# E6_Esp32_TS26C01_v2.net
KiCad netlist of a schematic drawn in EAGLE
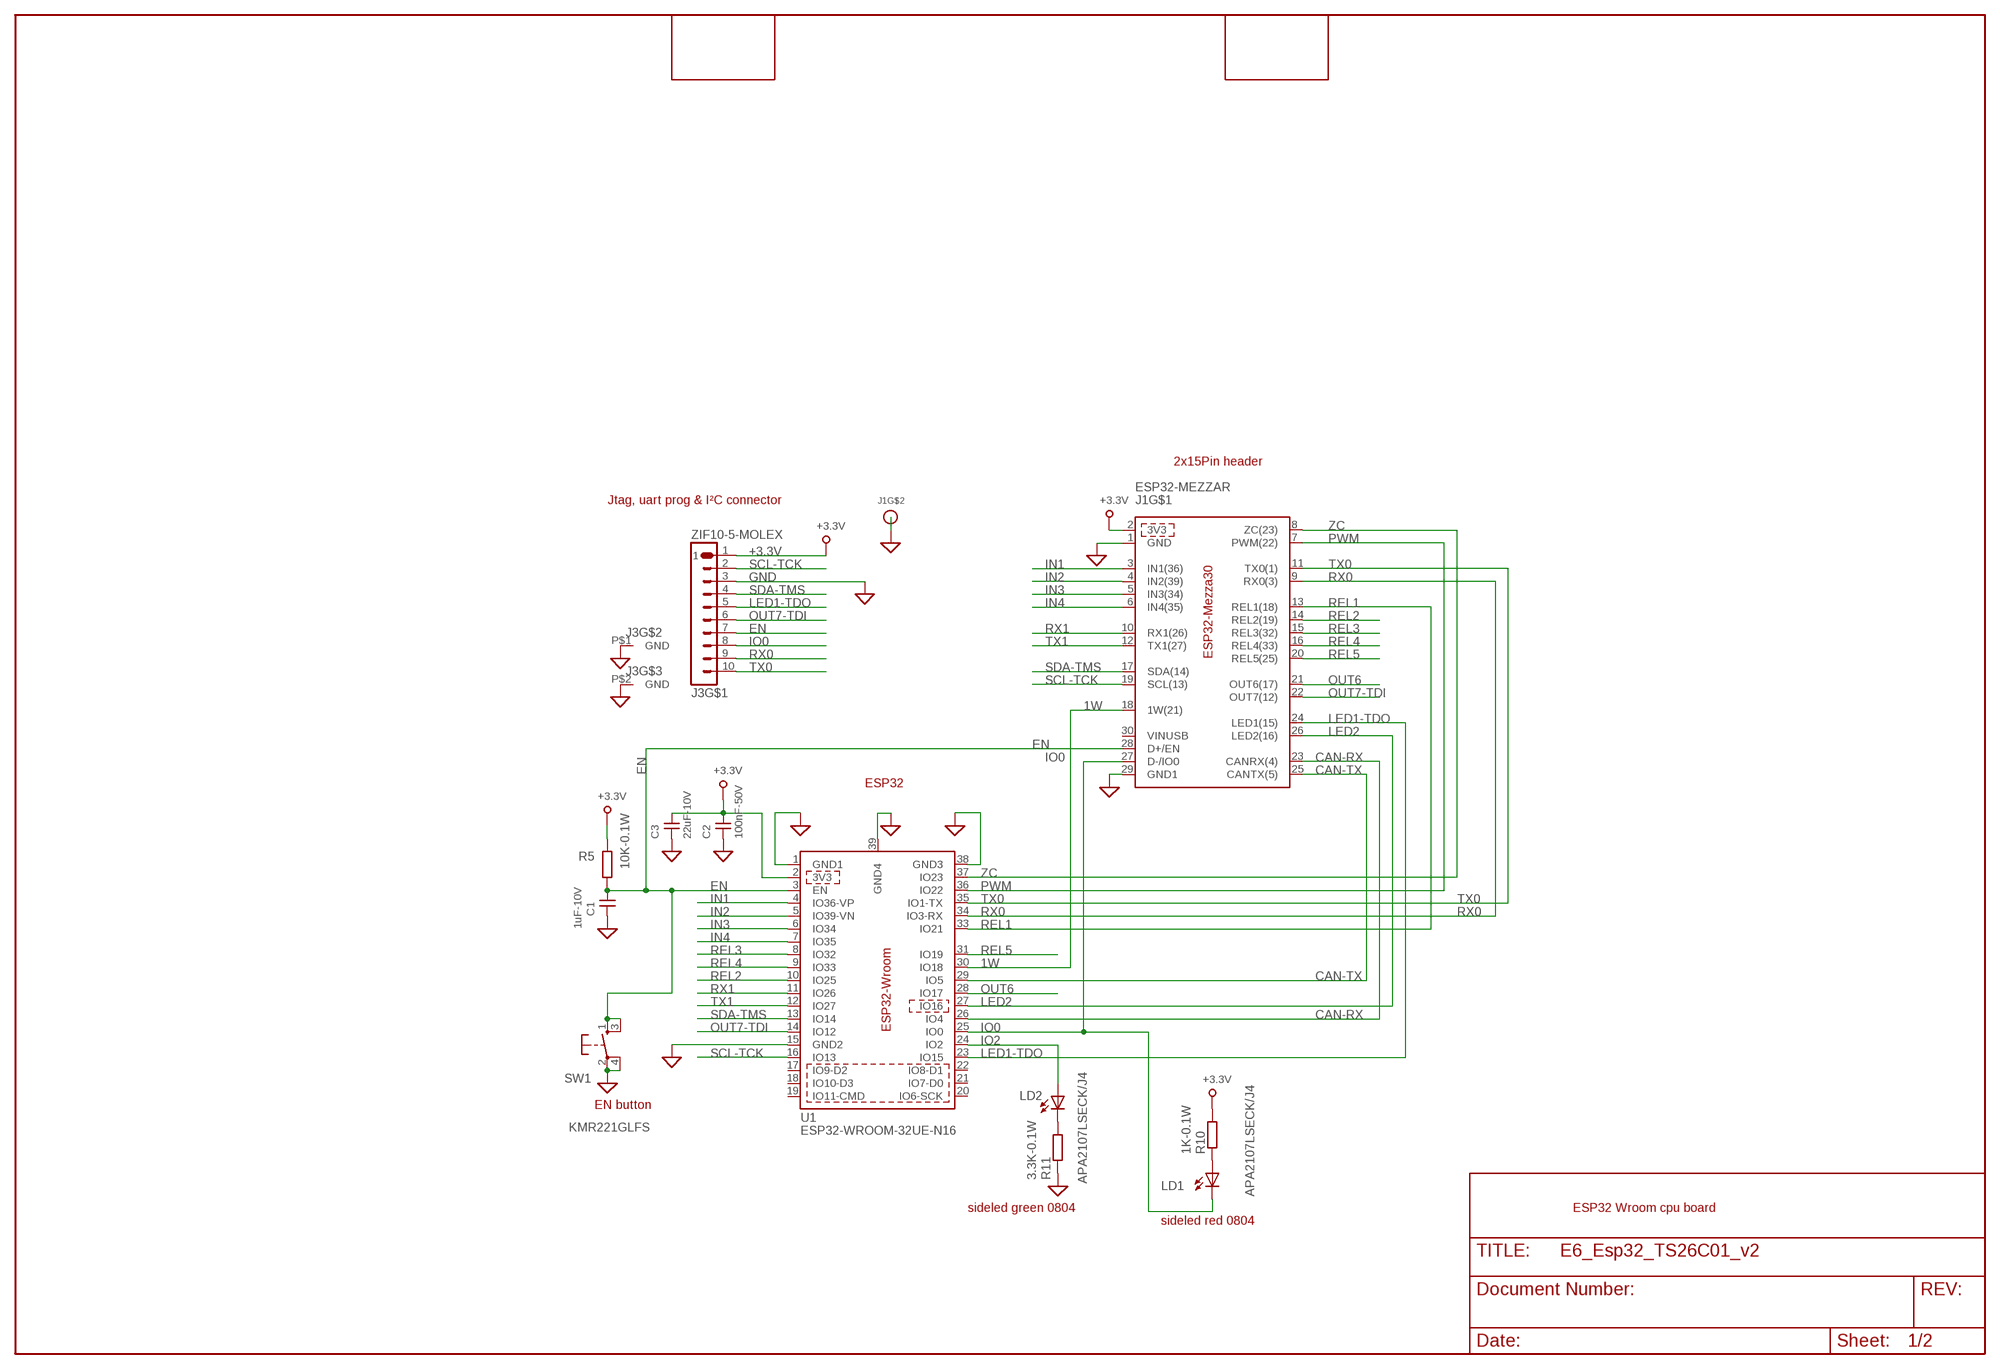
[diagram p0: schematic, sheet 1]
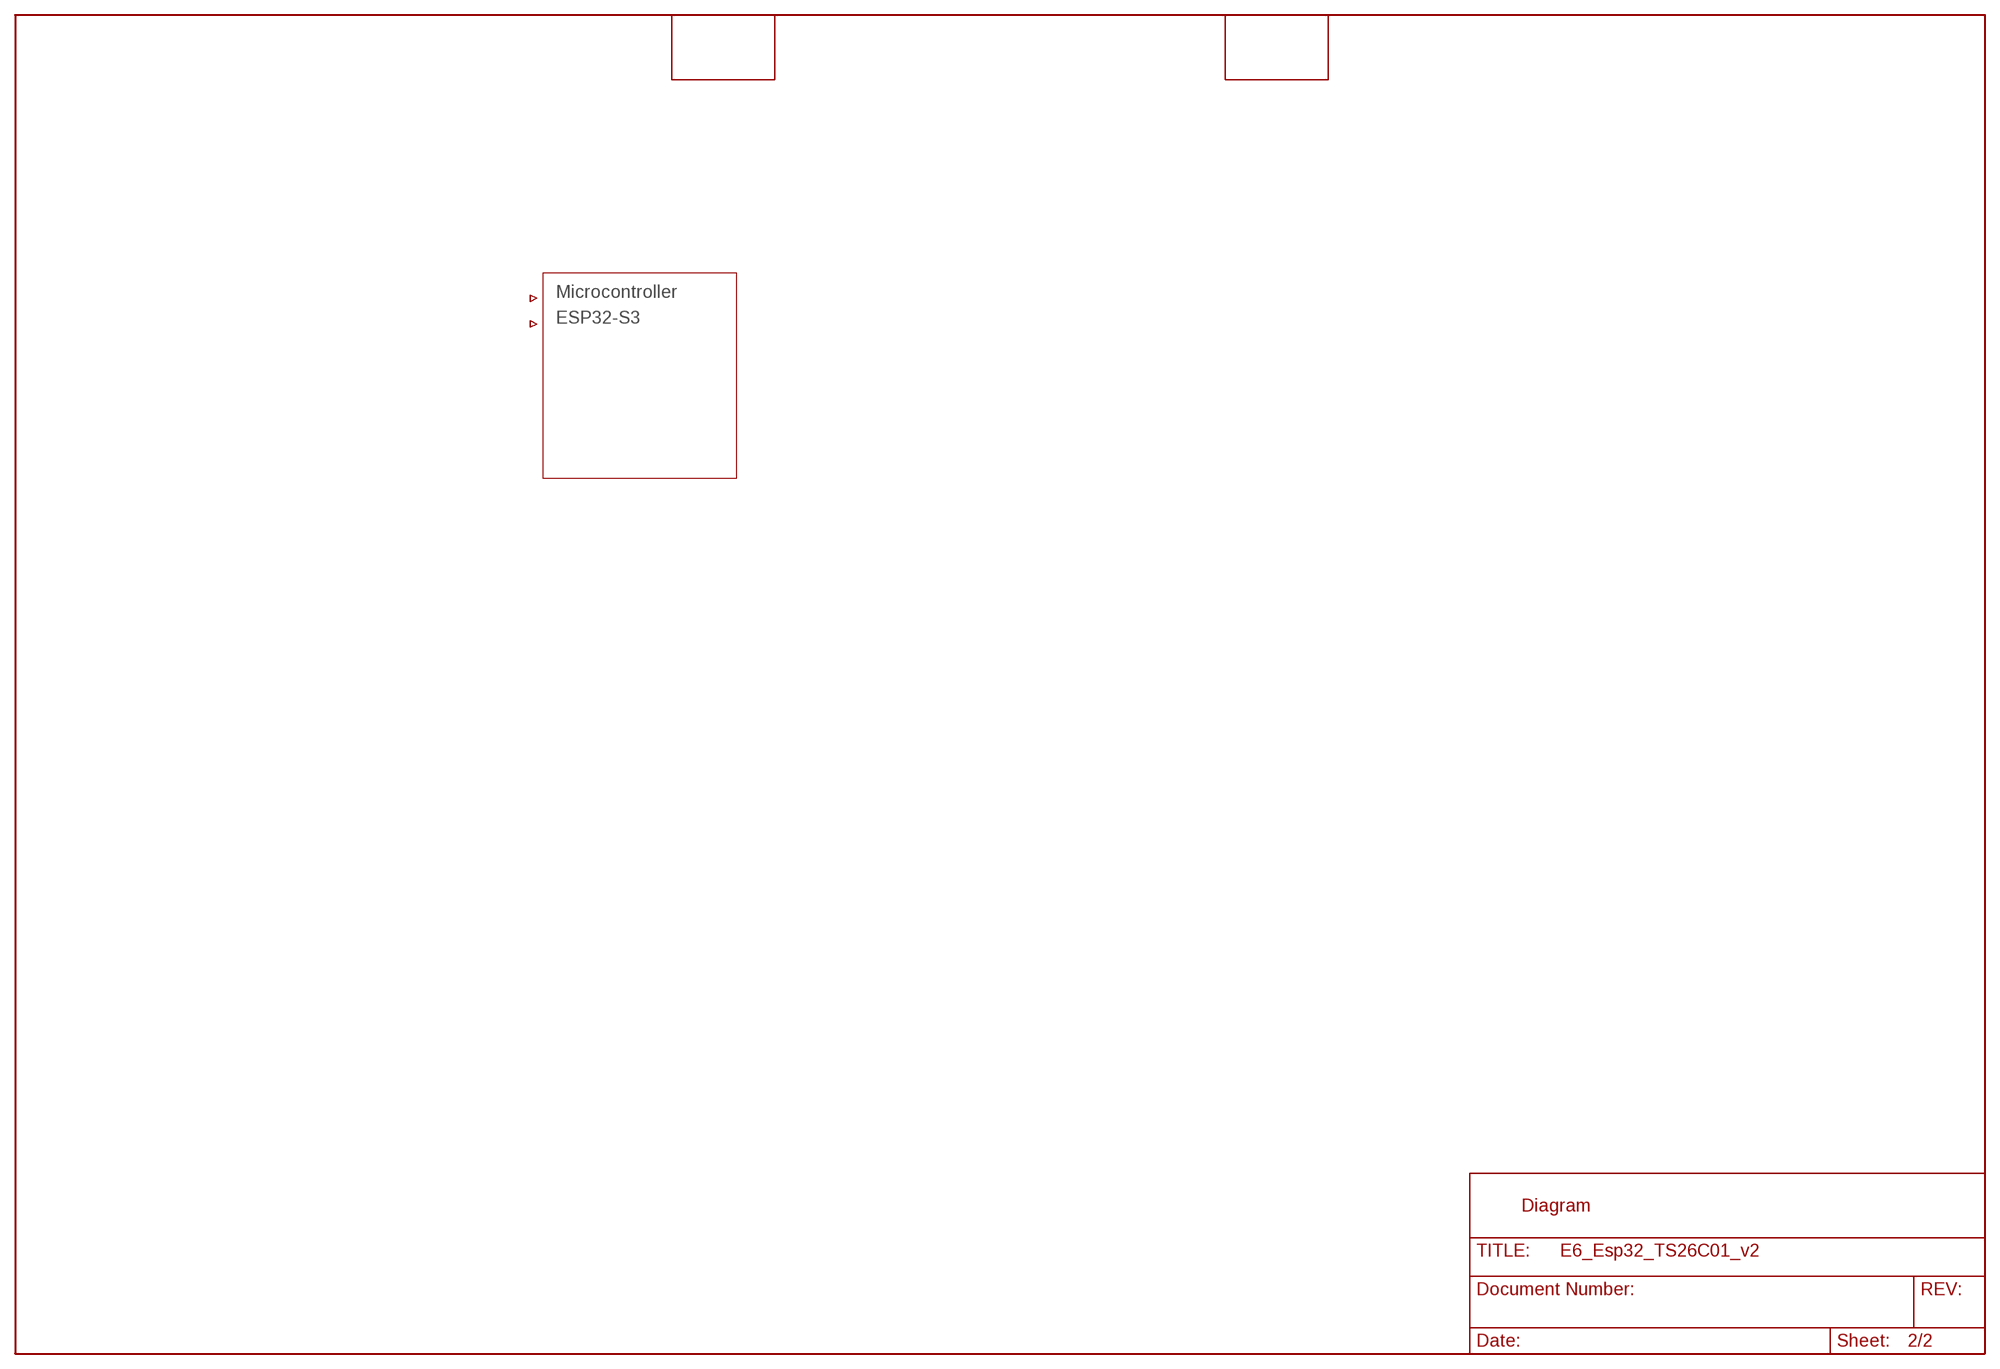
[diagram p1: schematic, sheet 2]

(export (version "E")
  (design (tool "Eeschema 10.0.6"))
  (components
    (comp (ref "C1")
      (value "1uF-10V")
      (footprint "eagle-import:C0603")
      (libsource (lib "eagle-import") (part "CAP-0603-L"))
    )
    (comp (ref "C2")
      (value "100nF-50V")
      (footprint "eagle-import:C0603")
      (libsource (lib "eagle-import") (part "CAP-0603-L"))
    )
    (comp (ref "C3")
      (value "22uF-10V")
      (footprint "eagle-import:C0603")
      (libsource (lib "eagle-import") (part "CAP-0603-L"))
    )
    (comp (ref "J1")
      (value "ESP32-MEZZAR")
      (footprint "eagle-import:ESP32-MEZZA25-R")
      (libsource (lib "eagle-import") (part "ESP32-MEZZAR"))
    )
    (comp (ref "J3")
      (value "ZIF10-5-MOLEX")
      (footprint "eagle-import:52746-1071-J")
      (libsource (lib "eagle-import") (part "ZIF10-5-MOLEXSTD"))
    )
    (comp (ref "LD1")
      (value "APA2107LSECK/J4")
      (footprint "eagle-import:SIDELED_0805")
      (libsource (lib "eagle-import") (part "SIDELED_0805"))
    )
    (comp (ref "LD2")
      (value "APA2107LSECK/J4")
      (footprint "eagle-import:SIDELED_0805")
      (libsource (lib "eagle-import") (part "SIDELED_0805"))
    )
    (comp (ref "R5")
      (value "10K-0.1W")
      (footprint "eagle-import:0603")
      (libsource (lib "eagle-import") (part "R-EU_R0603-S"))
    )
    (comp (ref "R10")
      (value "1K-0.1W")
      (footprint "eagle-import:0603")
      (libsource (lib "eagle-import") (part "R-EU_R0603-S"))
    )
    (comp (ref "R11")
      (value "3.3K-0.1W")
      (footprint "eagle-import:0603")
      (libsource (lib "eagle-import") (part "R-EU_R0603-S"))
    )
    (comp (ref "SW1")
      (value "KMR221GLFS")
      (footprint "eagle-import:SW-KMS-HOLE-NOGND")
      (libsource (lib "eagle-import") (part "SW-TACT-NOGNDSIDE"))
    )
    (comp (ref "U1")
      (value "ESP32-WROOM-32UE-N16")
      (footprint "eagle-import:ESP32-WROOM-32UE")
      (libsource (lib "eagle-import") (part "ESP32-WROOM-UE"))
    )
  )
  (nets
    (net (code "1") (name "+3.3V") (class "Default")
      (node (ref "C2") (pin "2") (pinfunction "2_2") (pintype "passive"))
      (node (ref "C3") (pin "2") (pinfunction "2_2") (pintype "passive"))
      (node (ref "J1") (pin "2") (pinfunction "3V3_2") (pintype "bidirectional"))
      (node (ref "J3") (pin "1") (pinfunction "1_1") (pintype "passive"))
      (node (ref "R10") (pin "1") (pinfunction "1_1") (pintype "passive"))
      (node (ref "R5") (pin "1") (pinfunction "1_1") (pintype "passive"))
      (node (ref "U1") (pin "2") (pinfunction "3V3_2") (pintype "power_in"))
    )
    (net (code "2") (name "1W") (class "Default")
      (node (ref "J1") (pin "18") (pinfunction "1W(21)_18") (pintype "bidirectional"))
      (node (ref "U1") (pin "30") (pinfunction "IO18_30") (pintype "bidirectional"))
    )
    (net (code "3") (name "CAN-RX") (class "Default")
      (node (ref "J1") (pin "23") (pinfunction "CANRX(4)_23") (pintype "bidirectional"))
      (node (ref "U1") (pin "26") (pinfunction "IO4_26") (pintype "bidirectional"))
    )
    (net (code "4") (name "CAN-TX") (class "Default")
      (node (ref "J1") (pin "25") (pinfunction "CANTX(5)_25") (pintype "bidirectional"))
      (node (ref "U1") (pin "29") (pinfunction "IO5_29") (pintype "bidirectional"))
    )
    (net (code "5") (name "EN") (class "Default")
      (node (ref "C1") (pin "2") (pinfunction "2_2") (pintype "passive"))
      (node (ref "J1") (pin "28") (pinfunction "D+/EN_28") (pintype "bidirectional"))
      (node (ref "J3") (pin "7") (pinfunction "7_7") (pintype "passive"))
      (node (ref "R5") (pin "2") (pinfunction "2_2") (pintype "passive"))
      (node (ref "SW1") (pin "1") (pinfunction "S_1") (pintype "passive"))
      (node (ref "SW1") (pin "3") (pinfunction "S_3") (pintype "passive"))
      (node (ref "U1") (pin "3") (pinfunction "EN_3") (pintype "bidirectional"))
    )
    (net (code "6") (name "GND") (class "Default")
      (node (ref "C1") (pin "1") (pinfunction "1_1") (pintype "passive"))
      (node (ref "C2") (pin "1") (pinfunction "1_1") (pintype "passive"))
      (node (ref "C3") (pin "1") (pinfunction "1_1") (pintype "passive"))
      (node (ref "J1") (pin "1") (pinfunction "GND_1") (pintype "power_in"))
      (node (ref "J1") (pin "29") (pinfunction "GND1_29") (pintype "power_in"))
      (node (ref "J1") (pin "31") (pinfunction "P$1_31") (pintype "passive"))
      (node (ref "J3") (pin "3") (pinfunction "3_3") (pintype "passive"))
      (node (ref "J3") (pin "P$1") (pinfunction "GND_P$1") (pintype "power_in"))
      (node (ref "J3") (pin "P$2") (pinfunction "GND_P$2") (pintype "power_in"))
      (node (ref "R11") (pin "2") (pinfunction "2_2") (pintype "passive"))
      (node (ref "SW1") (pin "2") (pinfunction "P_2") (pintype "passive"))
      (node (ref "SW1") (pin "4") (pinfunction "P_4") (pintype "passive"))
      (node (ref "U1") (pin "1") (pinfunction "GND1_1") (pintype "power_in"))
      (node (ref "U1") (pin "15") (pinfunction "GND2_15") (pintype "power_in"))
      (node (ref "U1") (pin "38") (pinfunction "GND3_38") (pintype "power_in"))
      (node (ref "U1") (pin "39") (pinfunction "GND4_39") (pintype "power_in"))
    )
    (net (code "7") (name "IN1") (class "Default")
      (node (ref "J1") (pin "3") (pinfunction "IN1(36)_3") (pintype "bidirectional"))
      (node (ref "U1") (pin "4") (pinfunction "IO36-VP_4") (pintype "bidirectional"))
    )
    (net (code "8") (name "IN2") (class "Default")
      (node (ref "J1") (pin "4") (pinfunction "IN2(39)_4") (pintype "bidirectional"))
      (node (ref "U1") (pin "5") (pinfunction "IO39-VN_5") (pintype "bidirectional"))
    )
    (net (code "9") (name "IN3") (class "Default")
      (node (ref "J1") (pin "5") (pinfunction "IN3(34)_5") (pintype "bidirectional"))
      (node (ref "U1") (pin "6") (pinfunction "IO34_6") (pintype "bidirectional"))
    )
    (net (code "10") (name "IN4") (class "Default")
      (node (ref "J1") (pin "6") (pinfunction "IN4(35)_6") (pintype "bidirectional"))
      (node (ref "U1") (pin "7") (pinfunction "IO35_7") (pintype "bidirectional"))
    )
    (net (code "11") (name "IO0") (class "Default")
      (node (ref "J1") (pin "27") (pinfunction "D-/IO0_27") (pintype "bidirectional"))
      (node (ref "J3") (pin "8") (pinfunction "8_8") (pintype "passive"))
      (node (ref "LD1") (pin "C") (pinfunction "C_C") (pintype "passive"))
      (node (ref "U1") (pin "25") (pinfunction "IO0_25") (pintype "bidirectional"))
    )
    (net (code "12") (name "IO2") (class "Default")
      (node (ref "LD2") (pin "A") (pinfunction "A_A") (pintype "passive"))
      (node (ref "U1") (pin "24") (pinfunction "IO2_24") (pintype "bidirectional"))
    )
    (net (code "13") (name "LED1-TDO") (class "Default")
      (node (ref "J1") (pin "24") (pinfunction "LED1(15)_24") (pintype "bidirectional"))
      (node (ref "J3") (pin "5") (pinfunction "5_5") (pintype "passive"))
      (node (ref "U1") (pin "23") (pinfunction "IO15_23") (pintype "bidirectional"))
    )
    (net (code "14") (name "LED2") (class "Default")
      (node (ref "J1") (pin "26") (pinfunction "LED2(16)_26") (pintype "bidirectional"))
      (node (ref "U1") (pin "27") (pinfunction "IO16_27") (pintype "bidirectional"))
    )
    (net (code "15") (name "Net-(LD1-PadA)") (class "Default")
      (node (ref "LD1") (pin "A") (pinfunction "A_A") (pintype "passive"))
      (node (ref "R10") (pin "2") (pinfunction "2_2") (pintype "passive"))
    )
    (net (code "16") (name "Net-(LD2-PadC)") (class "Default")
      (node (ref "LD2") (pin "C") (pinfunction "C_C") (pintype "passive"))
      (node (ref "R11") (pin "1") (pinfunction "1_1") (pintype "passive"))
    )
    (net (code "17") (name "OUT6") (class "Default")
      (node (ref "J1") (pin "21") (pinfunction "OUT6(17)_21") (pintype "bidirectional"))
      (node (ref "U1") (pin "28") (pinfunction "IO17_28") (pintype "bidirectional"))
    )
    (net (code "18") (name "OUT7-TDI") (class "Default")
      (node (ref "J1") (pin "22") (pinfunction "OUT7(12)_22") (pintype "bidirectional"))
      (node (ref "J3") (pin "6") (pinfunction "6_6") (pintype "passive"))
      (node (ref "U1") (pin "14") (pinfunction "IO12_14") (pintype "bidirectional"))
    )
    (net (code "19") (name "PWM") (class "Default")
      (node (ref "J1") (pin "7") (pinfunction "PWM(22)_7") (pintype "bidirectional"))
      (node (ref "U1") (pin "36") (pinfunction "IO22_36") (pintype "bidirectional"))
    )
    (net (code "20") (name "REL1") (class "Default")
      (node (ref "J1") (pin "13") (pinfunction "REL1(18)_13") (pintype "bidirectional"))
      (node (ref "U1") (pin "33") (pinfunction "IO21_33") (pintype "bidirectional"))
    )
    (net (code "21") (name "REL2") (class "Default")
      (node (ref "J1") (pin "14") (pinfunction "REL2(19)_14") (pintype "bidirectional"))
      (node (ref "U1") (pin "10") (pinfunction "IO25_10") (pintype "bidirectional"))
    )
    (net (code "22") (name "REL3") (class "Default")
      (node (ref "J1") (pin "15") (pinfunction "REL3(32)_15") (pintype "bidirectional"))
      (node (ref "U1") (pin "8") (pinfunction "IO32_8") (pintype "bidirectional"))
    )
    (net (code "23") (name "REL4") (class "Default")
      (node (ref "J1") (pin "16") (pinfunction "REL4(33)_16") (pintype "bidirectional"))
      (node (ref "U1") (pin "9") (pinfunction "IO33_9") (pintype "bidirectional"))
    )
    (net (code "24") (name "REL5") (class "Default")
      (node (ref "J1") (pin "20") (pinfunction "REL5(25)_20") (pintype "bidirectional"))
      (node (ref "U1") (pin "31") (pinfunction "IO19_31") (pintype "bidirectional"))
    )
    (net (code "25") (name "RX0") (class "Default")
      (node (ref "J1") (pin "9") (pinfunction "RX0(3)_9") (pintype "bidirectional"))
      (node (ref "J3") (pin "9") (pinfunction "9_9") (pintype "passive"))
      (node (ref "U1") (pin "34") (pinfunction "IO3-RX_34") (pintype "bidirectional"))
    )
    (net (code "26") (name "RX1") (class "Default")
      (node (ref "J1") (pin "10") (pinfunction "RX1(26)_10") (pintype "bidirectional"))
      (node (ref "U1") (pin "11") (pinfunction "IO26_11") (pintype "bidirectional"))
    )
    (net (code "27") (name "SCL-TCK") (class "Default")
      (node (ref "J1") (pin "19") (pinfunction "SCL(13)_19") (pintype "bidirectional"))
      (node (ref "J3") (pin "2") (pinfunction "2_2") (pintype "passive"))
      (node (ref "U1") (pin "16") (pinfunction "IO13_16") (pintype "bidirectional"))
    )
    (net (code "28") (name "SDA-TMS") (class "Default")
      (node (ref "J1") (pin "17") (pinfunction "SDA(14)_17") (pintype "bidirectional"))
      (node (ref "J3") (pin "4") (pinfunction "4_4") (pintype "passive"))
      (node (ref "U1") (pin "13") (pinfunction "IO14_13") (pintype "bidirectional"))
    )
    (net (code "29") (name "TX0") (class "Default")
      (node (ref "J1") (pin "11") (pinfunction "TX0(1)_11") (pintype "bidirectional"))
      (node (ref "J3") (pin "10") (pinfunction "10_10") (pintype "passive"))
      (node (ref "U1") (pin "35") (pinfunction "IO1-TX_35") (pintype "bidirectional"))
    )
    (net (code "30") (name "TX1") (class "Default")
      (node (ref "J1") (pin "12") (pinfunction "TX1(27)_12") (pintype "bidirectional"))
      (node (ref "U1") (pin "12") (pinfunction "IO27_12") (pintype "bidirectional"))
    )
    (net (code "31") (name "ZC") (class "Default")
      (node (ref "J1") (pin "8") (pinfunction "ZC(23)_8") (pintype "bidirectional"))
      (node (ref "U1") (pin "37") (pinfunction "IO23_37") (pintype "bidirectional"))
    )
    (net (code "32") (name "unconnected-(J1A-VINUSB-Pad30)") (class "Default")
      (node (ref "J1") (pin "30") (pinfunction "VINUSB_30") (pintype "bidirectional"))
    )
    (net (code "33") (name "unconnected-(U1-IO6-SCK-Pad20)") (class "Default")
      (node (ref "U1") (pin "20") (pinfunction "IO6-SCK_20") (pintype "no_connect"))
    )
    (net (code "34") (name "unconnected-(U1-IO7-D0-Pad21)") (class "Default")
      (node (ref "U1") (pin "21") (pinfunction "IO7-D0_21") (pintype "no_connect"))
    )
    (net (code "35") (name "unconnected-(U1-IO8-D1-Pad22)") (class "Default")
      (node (ref "U1") (pin "22") (pinfunction "IO8-D1_22") (pintype "no_connect"))
    )
    (net (code "36") (name "unconnected-(U1-IO9-D2-Pad17)") (class "Default")
      (node (ref "U1") (pin "17") (pinfunction "IO9-D2_17") (pintype "bidirectional"))
    )
    (net (code "37") (name "unconnected-(U1-IO10-D3-Pad18)") (class "Default")
      (node (ref "U1") (pin "18") (pinfunction "IO10-D3_18") (pintype "no_connect"))
    )
    (net (code "38") (name "unconnected-(U1-IO11-CMD-Pad19)") (class "Default")
      (node (ref "U1") (pin "19") (pinfunction "IO11-CMD_19") (pintype "no_connect"))
    )
  )
)
